# MotorControl.net
KiCad netlist of a schematic drawn in Altium Designer
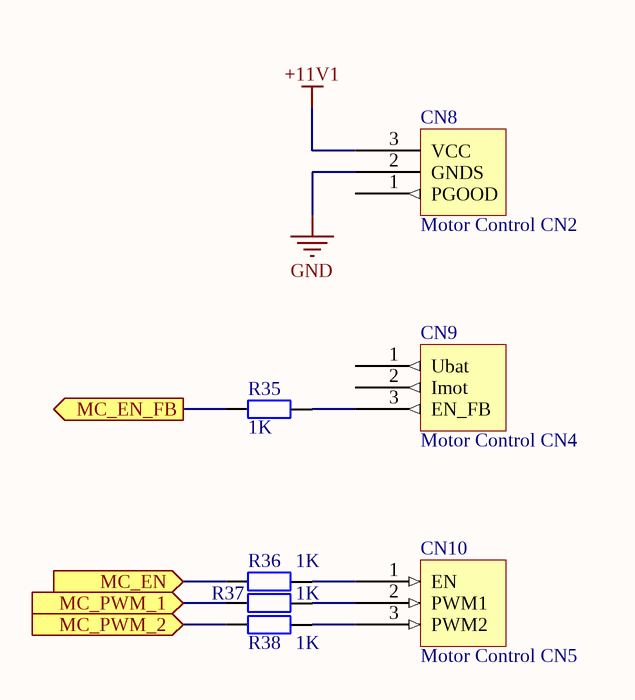
[diagram p0: MotorControl.SchDoc]

(export (version "E")
  (design (tool "Eeschema 10.0.6"))
  (components
    (comp (ref "CN8")
      (value "Motor Control CN2")
      (footprint "DC_Drive_CN_Stelvio")
      (description "CN2 connector on the Motor Control PCB")
      (libsource (lib "LKBulls2023") (part "Motor_Control_CN2"))
    )
    (comp (ref "CN9")
      (value "Motor Control CN4")
      (footprint "DC_Drive_CN_Stelvio")
      (description "CN4 connector on the Motor Control PCB")
      (libsource (lib "LKBulls2023") (part "Motor_Control_CN4"))
    )
    (comp (ref "CN10")
      (value "Motor Control CN5")
      (footprint "DC_Drive_CN_Stelvio")
      (description "CN5 connector on the Motor Control PCB")
      (libsource (lib "LKBulls2023") (part "Motor_Control_CN5"))
    )
    (comp (ref "R35")
      (value "1K")
      (footprint "FP_0805_RES")
      (description "Resistor")
      (fields (field (name "TOLERANCE") "5%") (field (name "POWER") "0.125W"))
      (libsource (lib "LKBulls2023") (part "RES"))
    )
    (comp (ref "R36")
      (value "1K")
      (footprint "FP_0805_RES")
      (description "Resistor")
      (fields (field (name "TOLERANCE") "5%") (field (name "POWER") "0.125W"))
      (libsource (lib "LKBulls2023") (part "RES"))
    )
    (comp (ref "R37")
      (value "1K")
      (footprint "FP_0805_RES")
      (description "Resistor")
      (fields (field (name "TOLERANCE") "5%") (field (name "POWER") "0.125W"))
      (libsource (lib "LKBulls2023") (part "RES"))
    )
    (comp (ref "R38")
      (value "1K")
      (footprint "FP_0805_RES")
      (description "Resistor")
      (fields (field (name "TOLERANCE") "5%") (field (name "POWER") "0.125W"))
      (libsource (lib "LKBulls2023") (part "RES"))
    )
  )
  (nets
    (net (code "1") (name "+11V1") (class "Default")
      (node (ref "CN8") (pin "3") (pinfunction "VCC_3") (pintype "passive"))
    )
    (net (code "2") (name "/MC_EN") (class "Default")
      (node (ref "R36") (pin "1") (pinfunction "1_1") (pintype "passive"))
    )
    (net (code "3") (name "/MC_EN_FB") (class "Default")
      (node (ref "R35") (pin "1") (pinfunction "1_1") (pintype "passive"))
    )
    (net (code "4") (name "/MC_PWM_1") (class "Default")
      (node (ref "R37") (pin "1") (pinfunction "1_1") (pintype "passive"))
    )
    (net (code "5") (name "/MC_PWM_2") (class "Default")
      (node (ref "R38") (pin "1") (pinfunction "1_1") (pintype "passive"))
    )
    (net (code "6") (name "GND") (class "Default")
      (node (ref "CN8") (pin "2") (pinfunction "GNDS_2") (pintype "passive"))
    )
    (net (code "7") (name "Net-(CN9-EN_FB)") (class "Default")
      (node (ref "CN9") (pin "3") (pinfunction "EN_FB_3") (pintype "output"))
      (node (ref "R35") (pin "2") (pinfunction "2_2") (pintype "passive"))
    )
    (net (code "8") (name "Net-(CN10-EN)") (class "Default")
      (node (ref "CN10") (pin "1") (pinfunction "EN_1") (pintype "input"))
      (node (ref "R36") (pin "2") (pinfunction "2_2") (pintype "passive"))
    )
    (net (code "9") (name "Net-(CN10-PWM1)") (class "Default")
      (node (ref "CN10") (pin "2") (pinfunction "PWM1_2") (pintype "input"))
      (node (ref "R37") (pin "2") (pinfunction "2_2") (pintype "passive"))
    )
    (net (code "10") (name "Net-(CN10-PWM2)") (class "Default")
      (node (ref "CN10") (pin "3") (pinfunction "PWM2_3") (pintype "input"))
      (node (ref "R38") (pin "2") (pinfunction "2_2") (pintype "passive"))
    )
    (net (code "11") (name "unconnected-(CN8-PGOOD-Pad1)") (class "Default")
      (node (ref "CN8") (pin "1") (pinfunction "PGOOD_1") (pintype "output"))
    )
    (net (code "12") (name "unconnected-(CN9-Imot-Pad2)") (class "Default")
      (node (ref "CN9") (pin "2") (pinfunction "Imot_2") (pintype "output"))
    )
    (net (code "13") (name "unconnected-(CN9-Ubat-Pad1)") (class "Default")
      (node (ref "CN9") (pin "1") (pinfunction "Ubat_1") (pintype "output"))
    )
  )
)
